# Iridium_9603_Antenna.net
KiCad netlist of a schematic drawn in EAGLE
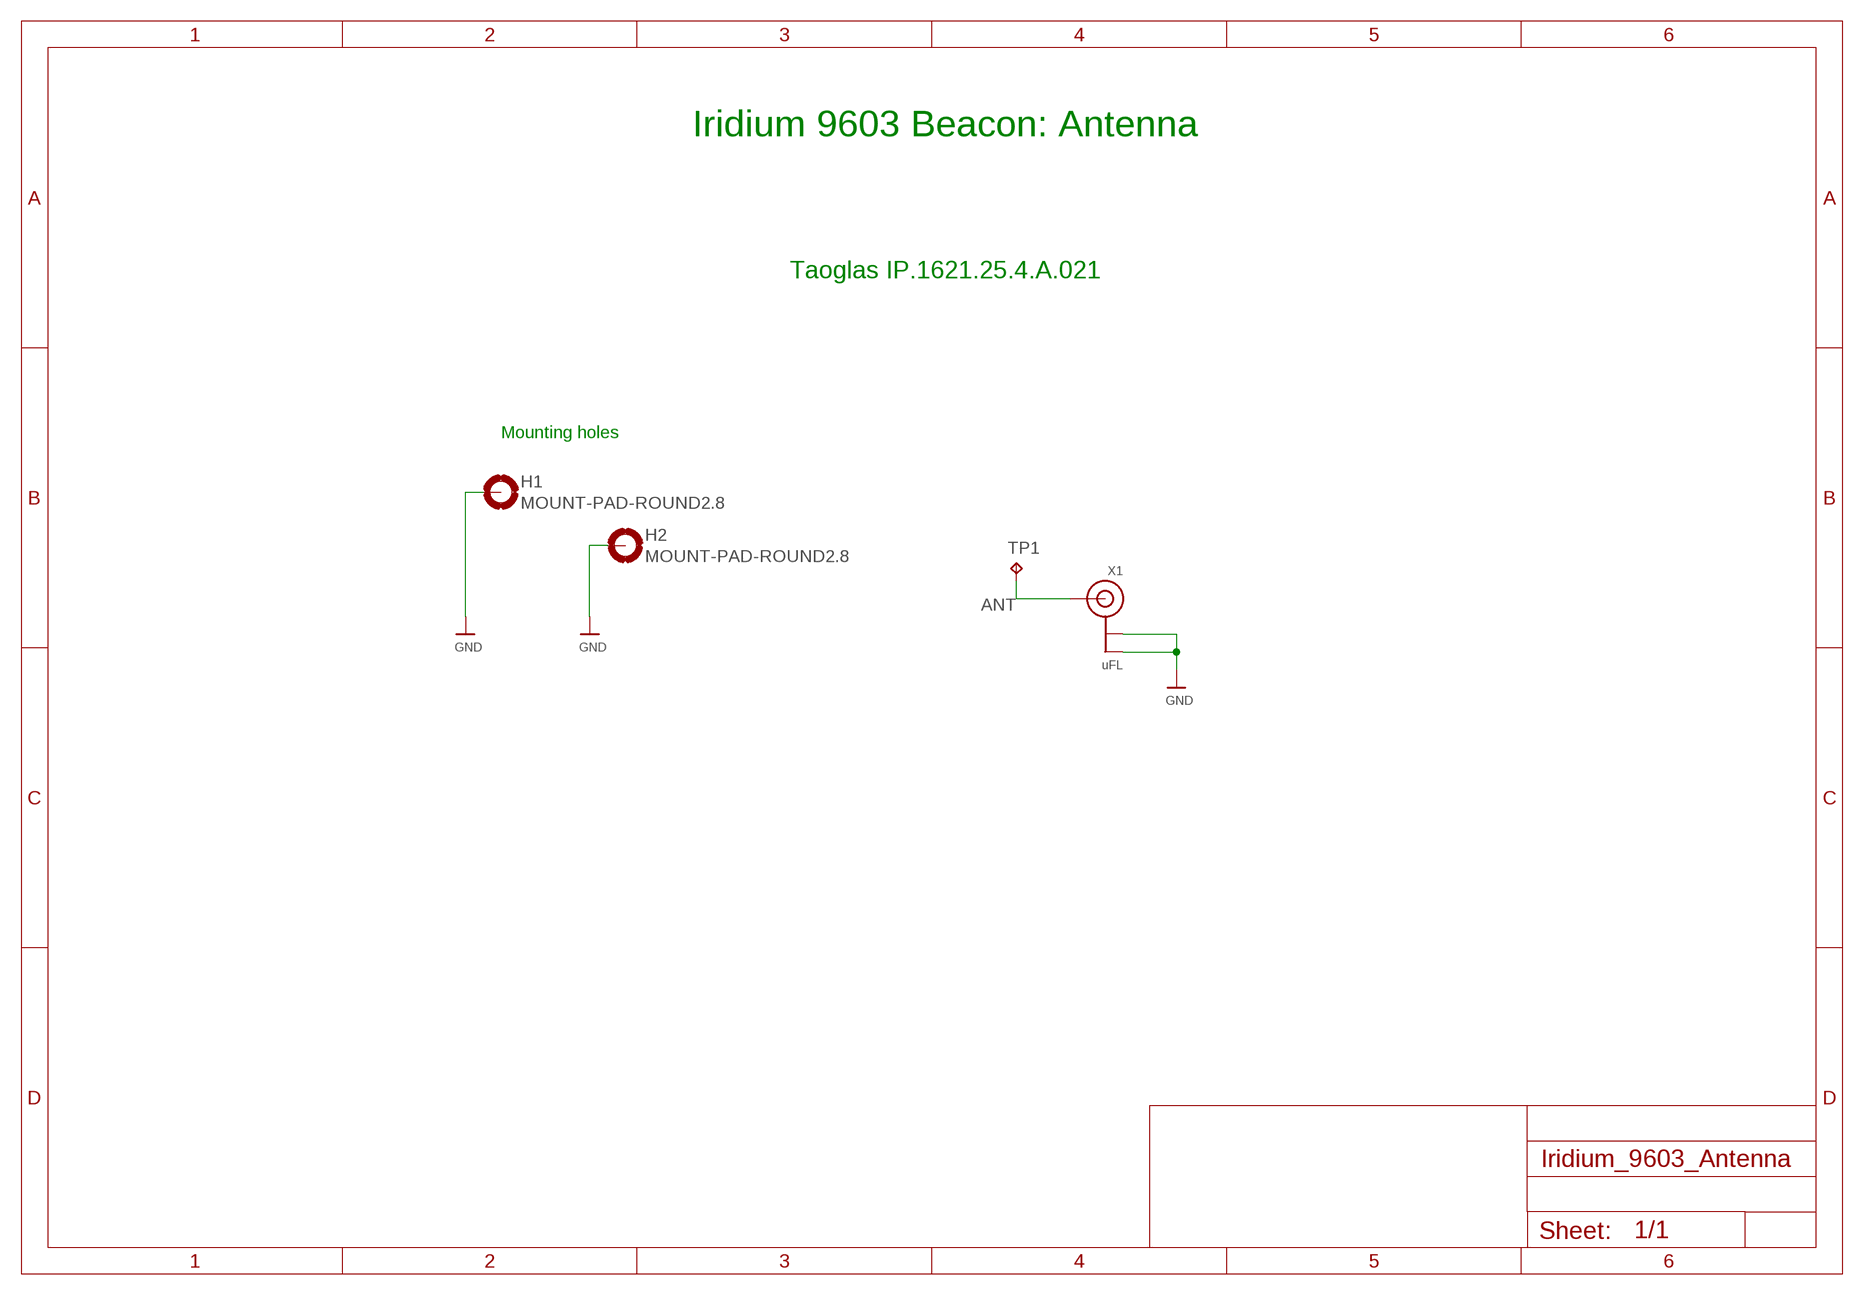
[diagram p0: schematic, sheet 1]

(export (version "E")
  (design (tool "Eeschema 10.0.6"))
  (components
    (comp (ref "H1")
      (value "MOUNT-PAD-ROUND2.8")
      (footprint "eagle-import:2,8-PAD")
      (libsource (lib "eagle-import") (part "MOUNT-PAD-ROUND2.8"))
    )
    (comp (ref "H2")
      (value "MOUNT-PAD-ROUND2.8")
      (footprint "eagle-import:2,8-PAD")
      (libsource (lib "eagle-import") (part "MOUNT-PAD-ROUND2.8"))
    )
    (comp (ref "TP1")
      (value "TPB2,54")
      (footprint "eagle-import:B2,54")
      (libsource (lib "eagle-import") (part "TPB2,54"))
    )
    (comp (ref "X1")
      (value "uFL")
      (footprint "eagle-import:U.FL")
      (libsource (lib "eagle-import") (part "ANTENNA_U.FL"))
    )
  )
  (nets
    (net (code "1") (name "/ANT") (class "Default")
      (node (ref "TP1") (pin "TP") (pinfunction "TP_TP") (pintype "input"))
      (node (ref "X1") (pin "3") (pinfunction "SIGNAL_3") (pintype "passive"))
    )
    (net (code "2") (name "GND") (class "Default")
      (node (ref "H1") (pin "B2,8") (pinfunction "MOUNT_B2,8") (pintype "passive"))
      (node (ref "H2") (pin "B2,8") (pinfunction "MOUNT_B2,8") (pintype "passive"))
      (node (ref "X1") (pin "1") (pinfunction "GND_1") (pintype "passive"))
      (node (ref "X1") (pin "2") (pinfunction "GND_2") (pintype "passive"))
    )
  )
)
